# Domino_Single_Ethernet.net
KiCad netlist of a schematic drawn in EAGLE
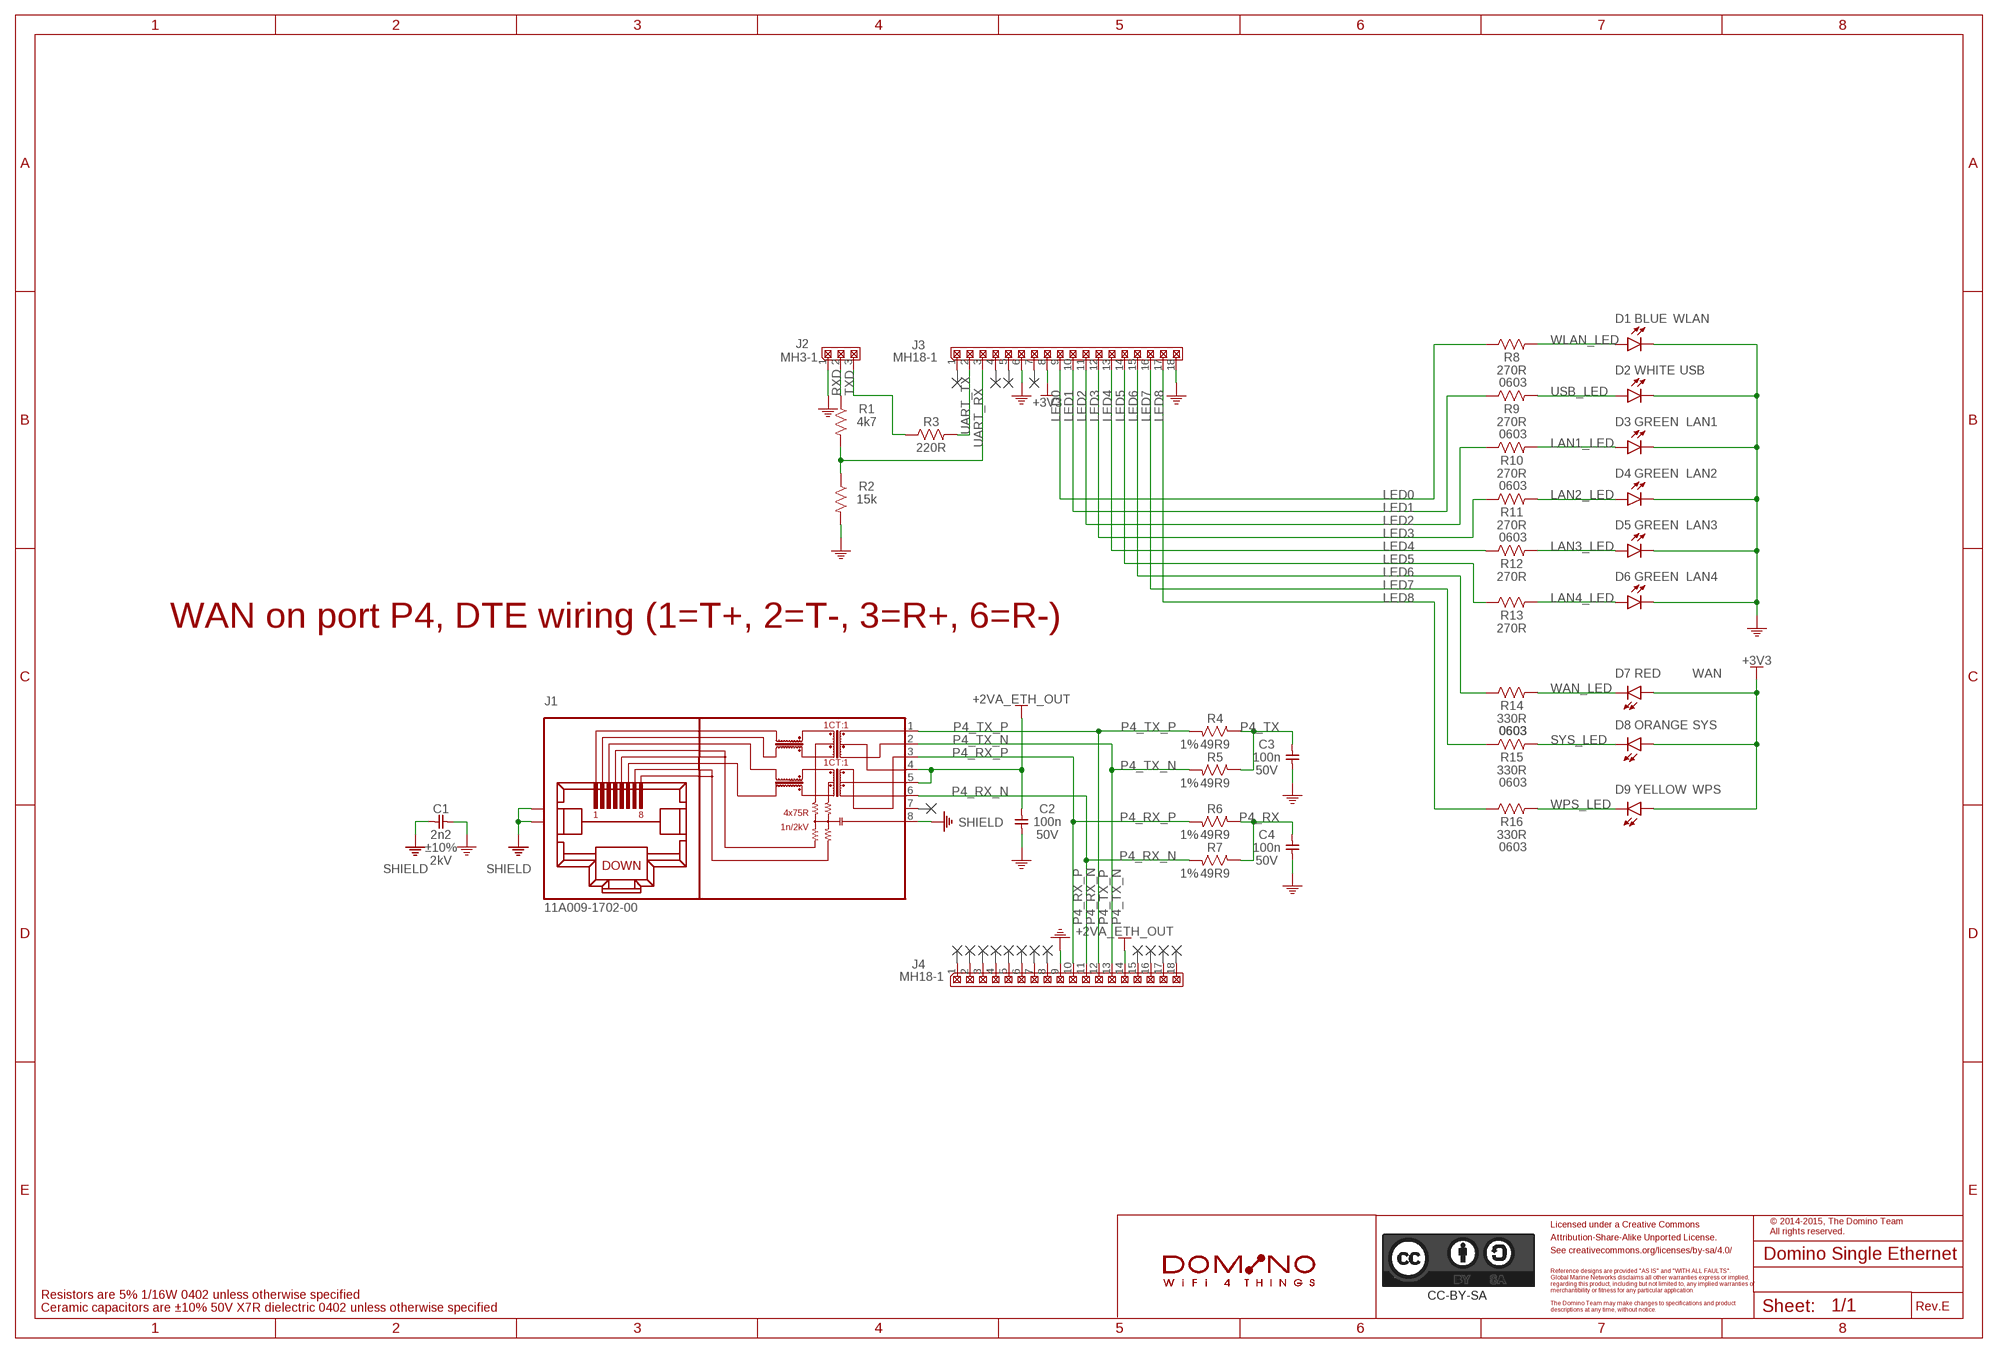
[diagram p0: schematic, sheet 1]

(export (version "E")
  (design (tool "Eeschema 10.0.6"))
  (components
    (comp (ref "C1")
      (value "2n2")
      (footprint "eagle-import:C1206")
      (fields
        (field (name "PARTNO") "C1210_2n2_X7R_10%_CER_2kV")
        (field (name "TOL") "±10%")
        (field (name "VOLT") "2kV")
      )
      (libsource (lib "eagle-import") (part "CAP_1206"))
    )
    (comp (ref "C2")
      (value "100n")
      (footprint "eagle-import:C0402")
      (fields (field (name "PARTNO") "C0402_100n_X7R_10%_CER_50V") (field (name "VOLT") "50V"))
      (libsource (lib "eagle-import") (part "CAP_0402"))
    )
    (comp (ref "C3")
      (value "100n")
      (footprint "eagle-import:C0402")
      (fields (field (name "PARTNO") "C0402_100n_X7R_10%_CER_50V") (field (name "VOLT") "50V"))
      (libsource (lib "eagle-import") (part "CAP_0402"))
    )
    (comp (ref "C4")
      (value "100n")
      (footprint "eagle-import:C0402")
      (fields (field (name "PARTNO") "C0402_100n_X7R_10%_CER_50V") (field (name "VOLT") "50V"))
      (libsource (lib "eagle-import") (part "CAP_0402"))
    )
    (comp (ref "CC-BY-SA1")
      (value "CC-BY-SA_LOGO")
      (footprint "eagle-import:CC-BY-SA_LOGO")
      (libsource (lib "eagle-import") (part "CC-BY-SA_LOGO"))
    )
    (comp (ref "D1")
      (value "BLUE")
      (footprint "eagle-import:LED0603")
      (fields (field (name "PARTNO") "LED0603-BLUE"))
      (libsource (lib "eagle-import") (part "LED_0603"))
    )
    (comp (ref "D2")
      (value "WHITE")
      (footprint "eagle-import:LED0603")
      (fields (field (name "PARTNO") "LED0603-WHITE"))
      (libsource (lib "eagle-import") (part "LED_0603"))
    )
    (comp (ref "D3")
      (value "GREEN")
      (footprint "eagle-import:LED0603")
      (fields (field (name "PARTNO") "LED0603-GREEN"))
      (libsource (lib "eagle-import") (part "LED_0603"))
    )
    (comp (ref "D4")
      (value "GREEN")
      (footprint "eagle-import:LED0603")
      (fields (field (name "PARTNO") "LED0603-GREEN"))
      (libsource (lib "eagle-import") (part "LED_0603"))
    )
    (comp (ref "D5")
      (value "GREEN")
      (footprint "eagle-import:LED0603")
      (fields (field (name "PARTNO") "LED0603-GREEN"))
      (libsource (lib "eagle-import") (part "LED_0603"))
    )
    (comp (ref "D6")
      (value "GREEN")
      (footprint "eagle-import:LED0603")
      (fields (field (name "PARTNO") "LED0603-GREEN"))
      (libsource (lib "eagle-import") (part "LED_0603"))
    )
    (comp (ref "D7")
      (value "RED")
      (footprint "eagle-import:LED0603")
      (fields (field (name "PARTNO") "LED0603-ORANGE"))
      (libsource (lib "eagle-import") (part "LED_0603"))
    )
    (comp (ref "D8")
      (value "ORANGE")
      (footprint "eagle-import:LED0603")
      (fields (field (name "PARTNO") "LED0603-ORANGE"))
      (libsource (lib "eagle-import") (part "LED_0603"))
    )
    (comp (ref "D9")
      (value "YELLOW")
      (footprint "eagle-import:LED0603")
      (fields (field (name "PARTNO") "LED0603-YELLOW"))
      (libsource (lib "eagle-import") (part "LED_0603"))
    )
    (comp (ref "J1")
      (value "11A009-1702-00")
      (footprint "eagle-import:11A009-1702-00")
      (libsource (lib "eagle-import") (part "11A009-1702-00"))
    )
    (comp (ref "J2")
      (value "MH3-1")
      (footprint "eagle-import:MH3-1-0.1")
      (fields (field (name "PARTNO") "MH3-1-0.1"))
      (libsource (lib "eagle-import") (part "MH3-1"))
    )
    (comp (ref "J3")
      (value "MH18-1")
      (footprint "eagle-import:MH18-1-0.1")
      (fields (field (name "PARTNO") "MH18-1-0.1"))
      (libsource (lib "eagle-import") (part "MH18-1"))
    )
    (comp (ref "J4")
      (value "MH18-1")
      (footprint "eagle-import:MH18-1-0.1")
      (fields (field (name "PARTNO") "MH18-1-0.1"))
      (libsource (lib "eagle-import") (part "MH18-1"))
    )
    (comp (ref "L1")
      (value "DOMINO_LOGO")
      (footprint "eagle-import:DOMINO_LOGO")
      (libsource (lib "eagle-import") (part "DOMINO_LOGO"))
    )
    (comp (ref "R1")
      (value "4k7")
      (footprint "eagle-import:R0402")
      (fields (field (name "PARTNO") "R0402_4k7_5%_62.5mW"))
      (libsource (lib "eagle-import") (part "RES_0402"))
    )
    (comp (ref "R2")
      (value "15k")
      (footprint "eagle-import:R0402")
      (fields (field (name "PARTNO") "R0402_15k_5%_62.5mW"))
      (libsource (lib "eagle-import") (part "RES_0402"))
    )
    (comp (ref "R3")
      (value "220R")
      (footprint "eagle-import:R0402")
      (fields (field (name "PARTNO") "R0402_220R_5%_62.5mW"))
      (libsource (lib "eagle-import") (part "RES_0402"))
    )
    (comp (ref "R4")
      (value "49R9")
      (footprint "eagle-import:R0402")
      (fields (field (name "PARTNO") "R0402_49R9_1%_62.5mW") (field (name "TOL") "1%"))
      (libsource (lib "eagle-import") (part "RES_0402"))
    )
    (comp (ref "R5")
      (value "49R9")
      (footprint "eagle-import:R0402")
      (fields (field (name "PARTNO") "R0402_49R9_1%_62.5mW") (field (name "TOL") "1%"))
      (libsource (lib "eagle-import") (part "RES_0402"))
    )
    (comp (ref "R6")
      (value "49R9")
      (footprint "eagle-import:R0402")
      (fields (field (name "PARTNO") "R0402_49R9_1%_62.5mW") (field (name "TOL") "1%"))
      (libsource (lib "eagle-import") (part "RES_0402"))
    )
    (comp (ref "R7")
      (value "49R9")
      (footprint "eagle-import:R0402")
      (fields (field (name "PARTNO") "R0402_49R9_1%_62.5mW") (field (name "TOL") "1%"))
      (libsource (lib "eagle-import") (part "RES_0402"))
    )
    (comp (ref "R8")
      (value "270R")
      (footprint "eagle-import:R0603")
      (fields (field (name "SIZE") "0603") (field (name "PARTNO") "R0603_270R_5%_125mW"))
      (libsource (lib "eagle-import") (part "RES_0603"))
    )
    (comp (ref "R9")
      (value "270R")
      (footprint "eagle-import:R0603")
      (fields (field (name "SIZE") "0603") (field (name "PARTNO") "R0603_270R_5%_125mW"))
      (libsource (lib "eagle-import") (part "RES_0603"))
    )
    (comp (ref "R10")
      (value "270R")
      (footprint "eagle-import:R0603")
      (fields (field (name "SIZE") "0603") (field (name "PARTNO") "R0603_270R_5%_125mW"))
      (libsource (lib "eagle-import") (part "RES_0603"))
    )
    (comp (ref "R11")
      (value "270R")
      (footprint "eagle-import:R0603")
      (fields (field (name "SIZE") "0603") (field (name "PARTNO") "R0603_270R_5%_125mW"))
      (libsource (lib "eagle-import") (part "RES_0603"))
    )
    (comp (ref "R12")
      (value "270R")
      (footprint "eagle-import:R0603")
      (fields (field (name "PARTNO") "R0603_270R_5%_125mW"))
      (libsource (lib "eagle-import") (part "RES_0603"))
    )
    (comp (ref "R13")
      (value "270R")
      (footprint "eagle-import:R0603")
      (fields (field (name "SIZE") "0603") (field (name "PARTNO") "R0603_270R_5%_125mW"))
      (libsource (lib "eagle-import") (part "RES_0603"))
    )
    (comp (ref "R14")
      (value "330R")
      (footprint "eagle-import:R0603")
      (fields (field (name "SIZE") "0603") (field (name "PARTNO") "R0603_330R_5%_125mW"))
      (libsource (lib "eagle-import") (part "RES_0603"))
    )
    (comp (ref "R15")
      (value "330R")
      (footprint "eagle-import:R0603")
      (fields (field (name "SIZE") "0603") (field (name "PARTNO") "R0603_330R_5%_125mW"))
      (libsource (lib "eagle-import") (part "RES_0603"))
    )
    (comp (ref "R16")
      (value "330R")
      (footprint "eagle-import:R0603")
      (fields (field (name "SIZE") "0603") (field (name "PARTNO") "R0603_330R_5%_125mW"))
      (libsource (lib "eagle-import") (part "RES_0603"))
    )
  )
  (nets
    (net (code "1") (name "+2VA_ETH_OUT") (class "Default")
      (node (ref "C2") (pin "2") (pinfunction "2_2") (pintype "passive"))
      (node (ref "J1") (pin "4") (pinfunction "P4_4") (pintype "passive"))
      (node (ref "J1") (pin "5") (pinfunction "P5_5") (pintype "passive"))
      (node (ref "J4") (pin "14") (pinfunction "14_14") (pintype "passive"))
    )
    (net (code "2") (name "+3V3") (class "Default")
      (node (ref "D7") (pin "2") (pinfunction "A_2") (pintype "passive"))
      (node (ref "D8") (pin "2") (pinfunction "A_2") (pintype "passive"))
      (node (ref "D9") (pin "2") (pinfunction "A_2") (pintype "passive"))
      (node (ref "J3") (pin "8") (pinfunction "8_8") (pintype "passive"))
    )
    (net (code "3") (name "/LAN1_LED") (class "Default")
      (node (ref "D3") (pin "2") (pinfunction "A_2") (pintype "passive"))
      (node (ref "R10") (pin "2") (pinfunction "2_2") (pintype "passive"))
    )
    (net (code "4") (name "/LAN2_LED") (class "Default")
      (node (ref "D4") (pin "2") (pinfunction "A_2") (pintype "passive"))
      (node (ref "R11") (pin "2") (pinfunction "2_2") (pintype "passive"))
    )
    (net (code "5") (name "/LAN3_LED") (class "Default")
      (node (ref "D5") (pin "2") (pinfunction "A_2") (pintype "passive"))
      (node (ref "R12") (pin "2") (pinfunction "2_2") (pintype "passive"))
    )
    (net (code "6") (name "/LAN4_LED") (class "Default")
      (node (ref "D6") (pin "2") (pinfunction "A_2") (pintype "passive"))
      (node (ref "R13") (pin "2") (pinfunction "2_2") (pintype "passive"))
    )
    (net (code "7") (name "/LED0") (class "Default")
      (node (ref "J3") (pin "9") (pinfunction "9_9") (pintype "passive"))
      (node (ref "R8") (pin "1") (pinfunction "1_1") (pintype "passive"))
    )
    (net (code "8") (name "/LED1") (class "Default")
      (node (ref "J3") (pin "10") (pinfunction "10_10") (pintype "passive"))
      (node (ref "R9") (pin "1") (pinfunction "1_1") (pintype "passive"))
    )
    (net (code "9") (name "/LED2") (class "Default")
      (node (ref "J3") (pin "11") (pinfunction "11_11") (pintype "passive"))
      (node (ref "R10") (pin "1") (pinfunction "1_1") (pintype "passive"))
    )
    (net (code "10") (name "/LED3") (class "Default")
      (node (ref "J3") (pin "12") (pinfunction "12_12") (pintype "passive"))
      (node (ref "R11") (pin "1") (pinfunction "1_1") (pintype "passive"))
    )
    (net (code "11") (name "/LED4") (class "Default")
      (node (ref "J3") (pin "13") (pinfunction "13_13") (pintype "passive"))
      (node (ref "R12") (pin "1") (pinfunction "1_1") (pintype "passive"))
    )
    (net (code "12") (name "/LED5") (class "Default")
      (node (ref "J3") (pin "14") (pinfunction "14_14") (pintype "passive"))
      (node (ref "R13") (pin "1") (pinfunction "1_1") (pintype "passive"))
    )
    (net (code "13") (name "/LED6") (class "Default")
      (node (ref "J3") (pin "15") (pinfunction "15_15") (pintype "passive"))
      (node (ref "R14") (pin "1") (pinfunction "1_1") (pintype "passive"))
    )
    (net (code "14") (name "/LED7") (class "Default")
      (node (ref "J3") (pin "16") (pinfunction "16_16") (pintype "passive"))
      (node (ref "R15") (pin "1") (pinfunction "1_1") (pintype "passive"))
    )
    (net (code "15") (name "/LED8") (class "Default")
      (node (ref "J3") (pin "17") (pinfunction "17_17") (pintype "passive"))
      (node (ref "R16") (pin "1") (pinfunction "1_1") (pintype "passive"))
    )
    (net (code "16") (name "/P4_RX") (class "Default")
      (node (ref "C4") (pin "2") (pinfunction "2_2") (pintype "passive"))
      (node (ref "R6") (pin "1") (pinfunction "1_1") (pintype "passive"))
      (node (ref "R7") (pin "1") (pinfunction "1_1") (pintype "passive"))
    )
    (net (code "17") (name "/P4_RX_N") (class "Default")
      (node (ref "J1") (pin "6") (pinfunction "P6_6") (pintype "passive"))
      (node (ref "J4") (pin "11") (pinfunction "11_11") (pintype "passive"))
      (node (ref "R7") (pin "2") (pinfunction "2_2") (pintype "passive"))
    )
    (net (code "18") (name "/P4_RX_P") (class "Default")
      (node (ref "J1") (pin "3") (pinfunction "P3_3") (pintype "passive"))
      (node (ref "J4") (pin "10") (pinfunction "10_10") (pintype "passive"))
      (node (ref "R6") (pin "2") (pinfunction "2_2") (pintype "passive"))
    )
    (net (code "19") (name "/P4_TX") (class "Default")
      (node (ref "C3") (pin "2") (pinfunction "2_2") (pintype "passive"))
      (node (ref "R4") (pin "1") (pinfunction "1_1") (pintype "passive"))
      (node (ref "R5") (pin "1") (pinfunction "1_1") (pintype "passive"))
    )
    (net (code "20") (name "/P4_TX_N") (class "Default")
      (node (ref "J1") (pin "2") (pinfunction "P2_2") (pintype "passive"))
      (node (ref "J4") (pin "13") (pinfunction "13_13") (pintype "passive"))
      (node (ref "R5") (pin "2") (pinfunction "2_2") (pintype "passive"))
    )
    (net (code "21") (name "/P4_TX_P") (class "Default")
      (node (ref "J1") (pin "1") (pinfunction "P1_1") (pintype "passive"))
      (node (ref "J4") (pin "12") (pinfunction "12_12") (pintype "passive"))
      (node (ref "R4") (pin "2") (pinfunction "2_2") (pintype "passive"))
    )
    (net (code "22") (name "/RXD") (class "Default")
      (node (ref "J2") (pin "2") (pinfunction "2_2") (pintype "passive"))
      (node (ref "R1") (pin "1") (pinfunction "1_1") (pintype "passive"))
    )
    (net (code "23") (name "/SYS_LED") (class "Default")
      (node (ref "D8") (pin "1") (pinfunction "C_1") (pintype "passive"))
      (node (ref "R15") (pin "2") (pinfunction "2_2") (pintype "passive"))
    )
    (net (code "24") (name "/TXD") (class "Default")
      (node (ref "J2") (pin "3") (pinfunction "3_3") (pintype "passive"))
      (node (ref "R3") (pin "1") (pinfunction "1_1") (pintype "passive"))
    )
    (net (code "25") (name "/UART_RX") (class "Default")
      (node (ref "J3") (pin "3") (pinfunction "3_3") (pintype "passive"))
      (node (ref "R1") (pin "2") (pinfunction "2_2") (pintype "passive"))
      (node (ref "R2") (pin "1") (pinfunction "1_1") (pintype "passive"))
    )
    (net (code "26") (name "/UART_TX") (class "Default")
      (node (ref "J3") (pin "2") (pinfunction "2_2") (pintype "passive"))
      (node (ref "R3") (pin "2") (pinfunction "2_2") (pintype "passive"))
    )
    (net (code "27") (name "/USB_LED") (class "Default")
      (node (ref "D2") (pin "2") (pinfunction "A_2") (pintype "passive"))
      (node (ref "R9") (pin "2") (pinfunction "2_2") (pintype "passive"))
    )
    (net (code "28") (name "/WAN_LED") (class "Default")
      (node (ref "D7") (pin "1") (pinfunction "C_1") (pintype "passive"))
      (node (ref "R14") (pin "2") (pinfunction "2_2") (pintype "passive"))
    )
    (net (code "29") (name "/WLAN_LED") (class "Default")
      (node (ref "D1") (pin "2") (pinfunction "A_2") (pintype "passive"))
      (node (ref "R8") (pin "2") (pinfunction "2_2") (pintype "passive"))
    )
    (net (code "30") (name "/WPS_LED") (class "Default")
      (node (ref "D9") (pin "1") (pinfunction "C_1") (pintype "passive"))
      (node (ref "R16") (pin "2") (pinfunction "2_2") (pintype "passive"))
    )
    (net (code "31") (name "GND") (class "Default")
      (node (ref "C1") (pin "1") (pinfunction "1_1") (pintype "passive"))
      (node (ref "C2") (pin "1") (pinfunction "1_1") (pintype "passive"))
      (node (ref "C3") (pin "1") (pinfunction "1_1") (pintype "passive"))
      (node (ref "C4") (pin "1") (pinfunction "1_1") (pintype "passive"))
      (node (ref "D1") (pin "1") (pinfunction "C_1") (pintype "passive"))
      (node (ref "D2") (pin "1") (pinfunction "C_1") (pintype "passive"))
      (node (ref "D3") (pin "1") (pinfunction "C_1") (pintype "passive"))
      (node (ref "D4") (pin "1") (pinfunction "C_1") (pintype "passive"))
      (node (ref "D5") (pin "1") (pinfunction "C_1") (pintype "passive"))
      (node (ref "D6") (pin "1") (pinfunction "C_1") (pintype "passive"))
      (node (ref "J2") (pin "1") (pinfunction "1_1") (pintype "passive"))
      (node (ref "J3") (pin "18") (pinfunction "18_18") (pintype "passive"))
      (node (ref "J3") (pin "6") (pinfunction "6_6") (pintype "passive"))
      (node (ref "J4") (pin "9") (pinfunction "9_9") (pintype "passive"))
      (node (ref "R2") (pin "2") (pinfunction "2_2") (pintype "passive"))
    )
    (net (code "32") (name "SHIELD") (class "Default")
      (node (ref "C1") (pin "2") (pinfunction "2_2") (pintype "passive"))
      (node (ref "J1") (pin "8") (pinfunction "P8_8") (pintype "power_in"))
      (node (ref "J1") (pin "SH$1") (pinfunction "SHIELD_SH$1") (pintype "power_in"))
      (node (ref "J1") (pin "SH$2") (pinfunction "SHIELD_SH$2") (pintype "power_in"))
    )
    (net (code "33") (name "unconnected-(J1-P7-Pad7)") (class "Default")
      (node (ref "J1") (pin "7") (pinfunction "P7_7") (pintype "no_connect"))
    )
    (net (code "34") (name "unconnected-(J3-Pad1)") (class "Default")
      (node (ref "J3") (pin "1") (pinfunction "1_1") (pintype "passive"))
    )
    (net (code "35") (name "unconnected-(J3-Pad4)") (class "Default")
      (node (ref "J3") (pin "4") (pinfunction "4_4") (pintype "passive"))
    )
    (net (code "36") (name "unconnected-(J3-Pad5)") (class "Default")
      (node (ref "J3") (pin "5") (pinfunction "5_5") (pintype "passive"))
    )
    (net (code "37") (name "unconnected-(J3-Pad7)") (class "Default")
      (node (ref "J3") (pin "7") (pinfunction "7_7") (pintype "passive"))
    )
    (net (code "38") (name "unconnected-(J4-Pad1)") (class "Default")
      (node (ref "J4") (pin "1") (pinfunction "1_1") (pintype "passive"))
    )
    (net (code "39") (name "unconnected-(J4-Pad2)") (class "Default")
      (node (ref "J4") (pin "2") (pinfunction "2_2") (pintype "passive"))
    )
    (net (code "40") (name "unconnected-(J4-Pad3)") (class "Default")
      (node (ref "J4") (pin "3") (pinfunction "3_3") (pintype "passive"))
    )
    (net (code "41") (name "unconnected-(J4-Pad4)") (class "Default")
      (node (ref "J4") (pin "4") (pinfunction "4_4") (pintype "passive"))
    )
    (net (code "42") (name "unconnected-(J4-Pad5)") (class "Default")
      (node (ref "J4") (pin "5") (pinfunction "5_5") (pintype "passive"))
    )
    (net (code "43") (name "unconnected-(J4-Pad6)") (class "Default")
      (node (ref "J4") (pin "6") (pinfunction "6_6") (pintype "passive"))
    )
    (net (code "44") (name "unconnected-(J4-Pad7)") (class "Default")
      (node (ref "J4") (pin "7") (pinfunction "7_7") (pintype "passive"))
    )
    (net (code "45") (name "unconnected-(J4-Pad8)") (class "Default")
      (node (ref "J4") (pin "8") (pinfunction "8_8") (pintype "passive"))
    )
    (net (code "46") (name "unconnected-(J4-Pad15)") (class "Default")
      (node (ref "J4") (pin "15") (pinfunction "15_15") (pintype "passive"))
    )
    (net (code "47") (name "unconnected-(J4-Pad16)") (class "Default")
      (node (ref "J4") (pin "16") (pinfunction "16_16") (pintype "passive"))
    )
    (net (code "48") (name "unconnected-(J4-Pad17)") (class "Default")
      (node (ref "J4") (pin "17") (pinfunction "17_17") (pintype "passive"))
    )
    (net (code "49") (name "unconnected-(J4-Pad18)") (class "Default")
      (node (ref "J4") (pin "18") (pinfunction "18_18") (pintype "passive"))
    )
  )
)
